# Battery_Charger.net
KiCad netlist of a schematic drawn in Altium Designer
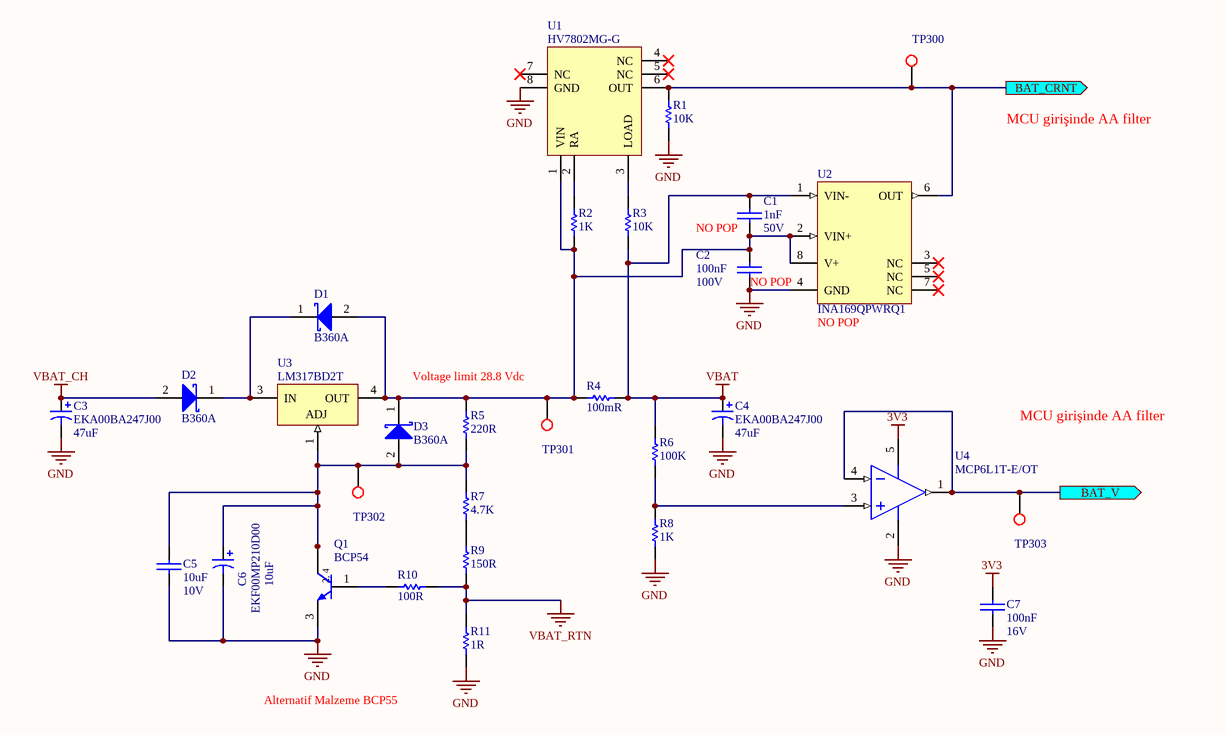
[diagram p0: Battery_Charger.SchDoc]

(export (version "E")
  (design (tool "Eeschema 10.0.6"))
  (components
    (comp (ref "C1")
      (value "1nF")
      (footprint "CAPC1005X06N")
      (description "CAP, CER, C0G, 1nF, %5, 50V, 0402")
      (fields
        (field (name "MANUFACTURER") "Murata")
        (field (name "MANUFACTURER PART NUMBER") "GRM1555C1H102JA01D")
        (field (name "OPERATING VOLTAGE") "50V")
        (field (name "ASSEMBLY") "NO POP")
      )
      (libsource (lib "Anime_Capacitor") (part "ACC0-0100-S272-0000"))
    )
    (comp (ref "C2")
      (value "100nF")
      (footprint "CAPC3216X09N")
      (description "CAP, CER, X7R, 100nF, %10, 100V, 1206")
      (fields
        (field (name "MANUFACTURER") "KEMET")
        (field (name "MANUFACTURER PART NUMBER") "C1206C104K1RACTU")
        (field (name "OPERATING VOLTAGE") "100V")
        (field (name "ASSEMBLY") "NO POP")
      )
      (libsource (lib "Anime_Capacitor") (part "ACC7-2100-S791-0000"))
    )
    (comp (ref "C3")
      (value "EKA00BA247J00")
      (footprint "CAPPR2.5-6.3X11")
      (description "Aluminum Electrolytic Capacitor, Radial Style with Long Leads: 47uF, 63V")
      (fields (field (name "ALTIUM_VALUE") "47uF") (field (name "PUBLISHER") "Altium Limited"))
      (libsource (lib "Vishay Roederstein Electrolytic Radial-Lead Capacitor") (part "EKA00BA247J00"))
    )
    (comp (ref "C4")
      (value "EKA00BA247J00")
      (footprint "CAPPR2.5-6.3X11")
      (description "Aluminum Electrolytic Capacitor, Radial Style with Long Leads: 47uF, 63V")
      (fields (field (name "ALTIUM_VALUE") "47uF") (field (name "PUBLISHER") "Altium Limited"))
      (libsource (lib "Vishay Roederstein Electrolytic Radial-Lead Capacitor") (part "EKA00BA247J00"))
    )
    (comp (ref "C5")
      (value "10uF")
      (footprint "CAPC2012X09N")
      (description "CAP, CER, X7R, 10uF, %10, 10V, 0805")
      (fields
        (field (name "MANUFACTURER") "Murata")
        (field (name "MANUFACTURER PART NUMBER") "GRM21BR71A106KE51L")
        (field (name "OPERATING VOLTAGE") "10V")
      )
      (libsource (lib "Anime_Capacitor") (part "ACC7-4100-S431-0000"))
    )
    (comp (ref "C6")
      (value "EKF00MP210D00")
      (footprint "CAPPR1.5-4X5")
      (description "Aluminum Electrolytic Capacitor, Radial Style with Long Leads: 10uF, 16V")
      (fields (field (name "ALTIUM_VALUE") "10uF") (field (name "PUBLISHER") "Altium Limited"))
      (libsource (lib "Vishay Roederstein Electrolytic Radial-Lead Capacitor") (part "EKF00MP210D00"))
    )
    (comp (ref "C7")
      (value "100nF")
      (footprint "CAPC1005X06N")
      (description "CAP, CER, X7R, 100nF, %10, 16V, 0402")
      (fields
        (field (name "MANUFACTURER") "Murata")
        (field (name "MANUFACTURER PART NUMBER") "GRM155R71C104KA88D")
        (field (name "OPERATING VOLTAGE") "16V")
      )
      (libsource (lib "Anime_Capacitor") (part "ACC7-2100-S241-0000"))
    )
    (comp (ref "D1")
      (value "B360A")
      (footprint "DIOM5226X23N")
      (description "Diode, Schottky, 0.7V @3A, 60V, SMA")
      (fields (field (name "MANUFACTURER PART NUMBER") "B360A-13-F") (field (name "MANUFACTURER") "Diodes"))
      (libsource (lib "Anime_Semiconductor") (part "AS15-930M-SI60-0001"))
    )
    (comp (ref "D2")
      (value "B360A")
      (footprint "DIOM5226X23N")
      (description "Diode, Schottky, 0.7V @3A, 60V, SMA")
      (fields (field (name "MANUFACTURER PART NUMBER") "B360A-13-F") (field (name "MANUFACTURER") "Diodes"))
      (libsource (lib "Anime_Semiconductor") (part "AS15-930M-SI60-0001"))
    )
    (comp (ref "D3")
      (value "B360A")
      (footprint "DIOM5226X23N")
      (description "Diode, Schottky, 0.7V @3A, 60V, SMA")
      (fields (field (name "MANUFACTURER PART NUMBER") "B360A-13-F") (field (name "MANUFACTURER") "Diodes"))
      (libsource (lib "Anime_Semiconductor") (part "AS15-930M-SI60-0001"))
    )
    (comp (ref "Q1")
      (value "BCP54")
      (footprint "SOT-223B_N")
      (description "NPN General Purpose Amplifier")
      (fields (field (name "PUBLISHER") "Altium Limited"))
      (libsource (lib "FSC Discrete BJT") (part "BCP54"))
    )
    (comp (ref "R1")
      (value "10K")
      (footprint "RESC1005X04N")
      (description "RES, E24, Thick Film, SMD, 10K, 1%, 0.1W, 0402")
      (fields
        (field (name "MANUFACTURER") "Panasonic")
        (field (name "MANUFACTURER PART NUMBER") "ERJ-2RKF1002X")
      )
      (libsource (lib "Anime_Resistor") (part "AR19-4100-S2B2-0000"))
    )
    (comp (ref "R2")
      (value "1K")
      (footprint "RESC1005X04N")
      (description "RES, E24, Thick Film, SMD, 1K, 1%, 0.1W, 0402")
      (fields
        (field (name "MANUFACTURER") "Panasonic")
        (field (name "MANUFACTURER PART NUMBER") "ERJ-2RKF1001X")
      )
      (libsource (lib "Anime_Resistor") (part "AR19-3100-S2B2-0000"))
    )
    (comp (ref "R3")
      (value "10K")
      (footprint "RESC1005X04N")
      (description "RES, E24, Thick Film, SMD, 10K, 1%, 0.1W, 0402")
      (fields
        (field (name "MANUFACTURER") "Panasonic")
        (field (name "MANUFACTURER PART NUMBER") "ERJ-2RKF1002X")
      )
      (libsource (lib "Anime_Resistor") (part "AR19-4100-S2B2-0000"))
    )
    (comp (ref "R4")
      (value "100mR")
      (footprint "RESC3216X08N")
      (description "RES, Thick Film, SMD, 100mR, 1%, 1W, 1206")
      (fields
        (field (name "MANUFACTURER") "Panasonic")
        (field (name "MANUFACTURER PART NUMBER") "ERJ-8BWFR100V")
      )
      (libsource (lib "Anime_Resistor") (part "AR19-Z100-S5D2-0000"))
    )
    (comp (ref "R5")
      (value "220R")
      (footprint "RESC2012X07N")
      (description "RES, E24, Thick Film, SMD, 220R, 1%, 0.125W, 0805")
      (fields
        (field (name "MANUFACTURER") "Panasonic")
        (field (name "MANUFACTURER PART NUMBER") "ERJ-6ENF2200V")
      )
      (libsource (lib "Anime_Resistor") (part "AR19-2220-S4B2-0000"))
    )
    (comp (ref "R6")
      (value "100K")
      (footprint "RESC1005X04N")
      (description "RES, E24, Thick Film, SMD, 100K, 1%, 0.1W, 0402")
      (fields
        (field (name "MANUFACTURER") "Panasonic")
        (field (name "MANUFACTURER PART NUMBER") "ERJ-2RKF1003X")
      )
      (libsource (lib "Anime_Resistor") (part "AR19-5100-S2B2-0000"))
    )
    (comp (ref "R7")
      (value "4.7K")
      (footprint "RESC2012X07N")
      (description "RES, E24, Thick Film, SMD, 4.7K, 1%, 0.125W, 0805")
      (fields
        (field (name "MANUFACTURER") "Panasonic")
        (field (name "MANUFACTURER PART NUMBER") "ERJ-6ENF4701V")
      )
      (libsource (lib "Anime_Resistor") (part "AR19-3470-S4B2-0000"))
    )
    (comp (ref "R8")
      (value "1K")
      (footprint "RESC1005X04N")
      (description "RES, E24, Thick Film, SMD, 1K, 1%, 0.1W, 0402")
      (fields
        (field (name "MANUFACTURER") "Panasonic")
        (field (name "MANUFACTURER PART NUMBER") "ERJ-2RKF1001X")
      )
      (libsource (lib "Anime_Resistor") (part "AR19-3100-S2B2-0000"))
    )
    (comp (ref "R9")
      (value "150R")
      (footprint "RESC2012X07N")
      (description "RES, E24, Thick Film, SMD, 150R, 1%, 0.125W, 0805")
      (fields
        (field (name "MANUFACTURER") "Panasonic")
        (field (name "MANUFACTURER PART NUMBER") "ERJ-6ENF1500V")
      )
      (libsource (lib "Anime_Resistor") (part "AR19-2150-S4B2-0000"))
    )
    (comp (ref "R10")
      (value "100R")
      (footprint "RESC2012X07N")
      (description "RES, E24, Thick Film, SMD, 100R, 1%, 0.125W, 0805")
      (fields
        (field (name "MANUFACTURER") "Panasonic")
        (field (name "MANUFACTURER PART NUMBER") "ERJ-6ENF1000V")
      )
      (libsource (lib "Anime_Resistor") (part "AR19-2100-S4B2-0000"))
    )
    (comp (ref "R11")
      (value "1R")
      (footprint "RESC3225X06N")
      (description "RES, Thick Film, SMD, 1R, 1%, 0.5W, 1210")
      (fields
        (field (name "MANUFACTURER") "Vishay")
        (field (name "MANUFACTURER PART NUMBER") "CRCW12101R00FKEA")
      )
      (libsource (lib "Anime_Resistor") (part "AR19-0100-S6B2-0000"))
    )
    (comp (ref "TP300")
      (value "AEMT-C00S-1000-0000")
      (footprint "TP100")
      (description "Test Point, Circular, 1mm")
      (libsource (lib "Anime_Electromechanical") (part "AEMT-C00S-1000-0000"))
    )
    (comp (ref "TP301")
      (value "AEMT-C00S-1000-0000")
      (footprint "TP100")
      (description "Test Point, Circular, 1mm")
      (libsource (lib "Anime_Electromechanical") (part "AEMT-C00S-1000-0000"))
    )
    (comp (ref "TP302")
      (value "AEMT-C00S-1000-0000")
      (footprint "TP100")
      (description "Test Point, Circular, 1mm")
      (libsource (lib "Anime_Electromechanical") (part "AEMT-C00S-1000-0000"))
    )
    (comp (ref "TP303")
      (value "AEMT-C00S-1000-0000")
      (footprint "TP100")
      (description "Test Point, Circular, 1mm")
      (libsource (lib "Anime_Electromechanical") (part "AEMT-C00S-1000-0000"))
    )
    (comp (ref "U1")
      (value "HV7802MG-G")
      (footprint "MSOP65P490X110-8N")
      (description "IC, PMIC, Current Monitor, HV7802MG-G, MSOP-8")
      (fields (field (name "MANUFACTURER") "Microchip"))
      (libsource (lib "Anime_IC") (part "AT82-0000-SMC0-1860"))
    )
    (comp (ref "U2")
      (value "INA169QPWRQ1")
      (footprint "TSOP65P640X120-8N")
      (description "IC, PMIC, Current Monitor, INA169QPWRQ1, TSSOP-8")
      (fields (field (name "MANUFACTURER") "Texas Instruments") (field (name "ASSEMBLY") "NO POP"))
      (libsource (lib "Anime_IC") (part "AT82-0000-SM90-0690"))
    )
    (comp (ref "U3")
      (value "LM317BD2T")
      (footprint "936-03")
      (description "Three-Terminal Adjustable Output Positive Voltage Regulator")
      (fields (field (name "PUBLISHER") "Altium Limited"))
      (libsource (lib "ON Semi Power Mgt Voltage Regulator") (part "LM317BD2T"))
    )
    (comp (ref "U4")
      (value "MCP6L1T-E/OT")
      (footprint "SOT-23-OT5_N")
      (description "2.8 MHz, 200 µA Op Amp, 5-Pin SOT-23, Extended Temperature Range, Tape and Reel")
      (fields (field (name "MANUFACTURER") "Microchip"))
      (libsource (lib "Microchip Linear") (part "MCP6L1T-E/OT"))
    )
  )
  (nets
    (net (code "1") (name "/BAT_CRNT") (class "Default")
      (node (ref "R1") (pin "2") (pinfunction "2_2") (pintype "passive"))
      (node (ref "TP300") (pin "1") (pintype "passive"))
      (node (ref "U1") (pin "6") (pinfunction "OUT_6") (pintype "passive"))
      (node (ref "U2") (pin "6") (pinfunction "OUT_6") (pintype "output"))
    )
    (net (code "2") (name "/BAT_V") (class "Default")
      (node (ref "TP303") (pin "1") (pintype "passive"))
      (node (ref "U4") (pin "1") (pinfunction "VOUT_1") (pintype "output"))
      (node (ref "U4") (pin "4") (pinfunction "VIN-_4") (pintype "input"))
    )
    (net (code "3") (name "3V3") (class "Default")
      (node (ref "C7") (pin "2") (pintype "passive"))
      (node (ref "U4") (pin "5") (pinfunction "VDD_5") (pintype "power_in"))
    )
    (net (code "4") (name "GND") (class "Default")
      (node (ref "C2") (pin "1") (pintype "passive"))
      (node (ref "C3") (pin "2") (pinfunction "2_2") (pintype "passive"))
      (node (ref "C4") (pin "2") (pinfunction "2_2") (pintype "passive"))
      (node (ref "C5") (pin "1") (pintype "passive"))
      (node (ref "C6") (pin "2") (pinfunction "2_2") (pintype "passive"))
      (node (ref "C7") (pin "1") (pintype "passive"))
      (node (ref "Q1") (pin "3") (pinfunction "E_3") (pintype "passive"))
      (node (ref "R1") (pin "1") (pinfunction "1_1") (pintype "passive"))
      (node (ref "R11") (pin "1") (pinfunction "1_1") (pintype "passive"))
      (node (ref "R8") (pin "1") (pinfunction "1_1") (pintype "passive"))
      (node (ref "U1") (pin "8") (pinfunction "GND_8") (pintype "power_in"))
      (node (ref "U2") (pin "4") (pinfunction "GND_4") (pintype "power_in"))
      (node (ref "U4") (pin "2") (pinfunction "VSS_2") (pintype "power_in"))
    )
    (net (code "5") (name "Net-(D1-A)") (class "Default")
      (node (ref "C1") (pin "1") (pintype "passive"))
      (node (ref "C2") (pin "2") (pintype "passive"))
      (node (ref "D1") (pin "2") (pinfunction "A_2") (pintype "passive"))
      (node (ref "D3") (pin "1") (pinfunction "K_1") (pintype "passive"))
      (node (ref "R2") (pin "1") (pinfunction "1_1") (pintype "passive"))
      (node (ref "R4") (pin "1") (pinfunction "1_1") (pintype "passive"))
      (node (ref "R5") (pin "2") (pinfunction "2_2") (pintype "passive"))
      (node (ref "TP301") (pin "1") (pintype "passive"))
      (node (ref "U1") (pin "1") (pinfunction "VIN_1") (pintype "passive"))
      (node (ref "U2") (pin "2") (pinfunction "VIN+_2") (pintype "input"))
      (node (ref "U2") (pin "8") (pinfunction "V+_8") (pintype "power_in"))
      (node (ref "U3") (pin "4") (pinfunction "OUT_4") (pintype "power_in"))
    )
    (net (code "6") (name "Net-(D1-K)") (class "Default")
      (node (ref "D1") (pin "1") (pinfunction "K_1") (pintype "passive"))
      (node (ref "D2") (pin "1") (pinfunction "K_1") (pintype "passive"))
      (node (ref "U3") (pin "3") (pinfunction "IN_3") (pintype "power_in"))
    )
    (net (code "7") (name "Net-(D3-A)") (class "Default")
      (node (ref "C5") (pin "2") (pintype "passive"))
      (node (ref "C6") (pin "1") (pinfunction "1_1") (pintype "passive"))
      (node (ref "D3") (pin "2") (pinfunction "A_2") (pintype "passive"))
      (node (ref "Q1") (pin "2") (pinfunction "C_2") (pintype "passive"))
      (node (ref "Q1") (pin "4") (pinfunction "C_4") (pintype "passive"))
      (node (ref "R5") (pin "1") (pinfunction "1_1") (pintype "passive"))
      (node (ref "R7") (pin "2") (pinfunction "2_2") (pintype "passive"))
      (node (ref "TP302") (pin "1") (pintype "passive"))
      (node (ref "U3") (pin "1") (pinfunction "ADJ_1") (pintype "input"))
    )
    (net (code "8") (name "Net-(Q1-B)") (class "Default")
      (node (ref "Q1") (pin "1") (pinfunction "B_1") (pintype "passive"))
      (node (ref "R10") (pin "1") (pinfunction "1_1") (pintype "passive"))
    )
    (net (code "9") (name "Net-(R7-Pad1)") (class "Default")
      (node (ref "R7") (pin "1") (pinfunction "1_1") (pintype "passive"))
      (node (ref "R9") (pin "2") (pinfunction "2_2") (pintype "passive"))
    )
    (net (code "10") (name "Net-(U1-LOAD)") (class "Default")
      (node (ref "R3") (pin "2") (pinfunction "2_2") (pintype "passive"))
      (node (ref "U1") (pin "3") (pinfunction "LOAD_3") (pintype "passive"))
    )
    (net (code "11") (name "Net-(U1-RA)") (class "Default")
      (node (ref "R2") (pin "2") (pinfunction "2_2") (pintype "passive"))
      (node (ref "U1") (pin "2") (pinfunction "RA_2") (pintype "passive"))
    )
    (net (code "12") (name "Net-(U4-VIN+)") (class "Default")
      (node (ref "R6") (pin "1") (pinfunction "1_1") (pintype "passive"))
      (node (ref "R8") (pin "2") (pinfunction "2_2") (pintype "passive"))
      (node (ref "U4") (pin "3") (pinfunction "VIN+_3") (pintype "input"))
    )
    (net (code "13") (name "VBAT") (class "Default")
      (node (ref "C1") (pin "2") (pintype "passive"))
      (node (ref "C4") (pin "1") (pinfunction "1_1") (pintype "passive"))
      (node (ref "R3") (pin "1") (pinfunction "1_1") (pintype "passive"))
      (node (ref "R4") (pin "2") (pinfunction "2_2") (pintype "passive"))
      (node (ref "R6") (pin "2") (pinfunction "2_2") (pintype "passive"))
      (node (ref "U2") (pin "1") (pinfunction "VIN-_1") (pintype "input"))
    )
    (net (code "14") (name "VBAT_CH") (class "Default")
      (node (ref "C3") (pin "1") (pinfunction "1_1") (pintype "passive"))
      (node (ref "D2") (pin "2") (pinfunction "A_2") (pintype "passive"))
    )
    (net (code "15") (name "VBAT_RTN") (class "Default")
      (node (ref "R10") (pin "2") (pinfunction "2_2") (pintype "passive"))
      (node (ref "R11") (pin "2") (pinfunction "2_2") (pintype "passive"))
      (node (ref "R9") (pin "1") (pinfunction "1_1") (pintype "passive"))
    )
    (net (code "16") (name "unconnected-(U1-NC-Pad4)") (class "Default")
      (node (ref "U1") (pin "4") (pinfunction "NC_4") (pintype "passive+no_connect"))
    )
    (net (code "17") (name "unconnected-(U1-NC-Pad5)") (class "Default")
      (node (ref "U1") (pin "5") (pinfunction "NC_5") (pintype "passive+no_connect"))
    )
    (net (code "18") (name "unconnected-(U1-NC-Pad7)") (class "Default")
      (node (ref "U1") (pin "7") (pinfunction "NC_7") (pintype "passive+no_connect"))
    )
    (net (code "19") (name "unconnected-(U2-NC-Pad3)") (class "Default")
      (node (ref "U2") (pin "3") (pinfunction "NC_3") (pintype "passive+no_connect"))
    )
    (net (code "20") (name "unconnected-(U2-NC-Pad5)") (class "Default")
      (node (ref "U2") (pin "5") (pinfunction "NC_5") (pintype "passive+no_connect"))
    )
    (net (code "21") (name "unconnected-(U2-NC-Pad7)") (class "Default")
      (node (ref "U2") (pin "7") (pinfunction "NC_7") (pintype "passive+no_connect"))
    )
  )
)
